# modem2_double.net
KiCad netlist of a schematic drawn in EAGLE
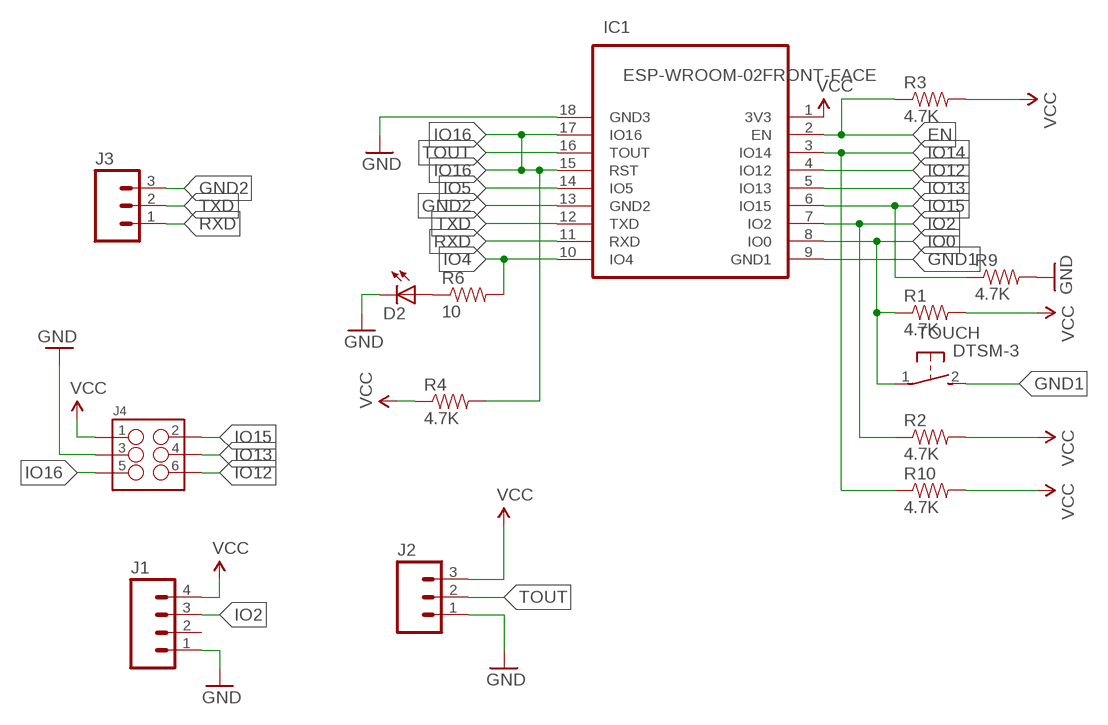
[diagram p0: schematic, sheet 1]

(export (version "E")
  (design (tool "Eeschema 10.0.6"))
  (components
    (comp (ref "D2")
      (value "LEDCHIPLED_0805")
      (footprint "eagle-import:CHIPLED_0805")
      (libsource (lib "eagle-import") (part "LEDCHIPLED_0805"))
    )
    (comp (ref "IC1")
      (value "ESP-WROOM-02FRONT-FACE")
      (footprint "eagle-import:FRONT-FACE")
      (libsource (lib "eagle-import") (part "ESP-WROOM-02FRONT-FACE"))
    )
    (comp (ref "J1")
      (value "M04NO_SILK_ALL_ROUND")
      (footprint "eagle-import:1X04_NO_SILK_ALL_ROUND")
      (libsource (lib "eagle-import") (part "M04NO_SILK_ALL_ROUND"))
    )
    (comp (ref "J2")
      (value "M03PTH")
      (footprint "eagle-import:1X03")
      (libsource (lib "eagle-import") (part "M03PTH"))
    )
    (comp (ref "J3")
      (value "M031X03_NO_SILK")
      (footprint "eagle-import:1X03_NO_SILK")
      (libsource (lib "eagle-import") (part "M031X03_NO_SILK"))
    )
    (comp (ref "J4")
      (value "M03X2SHROUD")
      (footprint "eagle-import:2X3-SHROUDED")
      (libsource (lib "eagle-import") (part "M03X2SHROUD"))
    )
    (comp (ref "R1")
      (value "4.7K")
      (footprint "eagle-import:0805")
      (libsource (lib "eagle-import") (part "RESISTOR0805-RES"))
    )
    (comp (ref "R2")
      (value "4.7K")
      (footprint "eagle-import:0805")
      (libsource (lib "eagle-import") (part "RESISTOR0805-RES"))
    )
    (comp (ref "R3")
      (value "4.7K")
      (footprint "eagle-import:0805")
      (libsource (lib "eagle-import") (part "RESISTOR0805-RES"))
    )
    (comp (ref "R4")
      (value "4.7K")
      (footprint "eagle-import:0805")
      (libsource (lib "eagle-import") (part "RESISTOR0805-RES"))
    )
    (comp (ref "R6")
      (value "10")
      (footprint "eagle-import:0805")
      (libsource (lib "eagle-import") (part "RESISTOR0805-RES"))
    )
    (comp (ref "R9")
      (value "4.7K")
      (footprint "eagle-import:0805")
      (libsource (lib "eagle-import") (part "RESISTOR0805-RES"))
    )
    (comp (ref "R10")
      (value "4.7K")
      (footprint "eagle-import:0805")
      (libsource (lib "eagle-import") (part "RESISTOR0805-RES"))
    )
    (comp (ref "TOUCH")
      (value "DTSM-3")
      (footprint "eagle-import:DTSM-3")
      (libsource (lib "eagle-import") (part "DTSM-3"))
    )
  )
  (nets
    (net (code "1") (name "EN") (class "Default")
      (node (ref "IC1") (pin "2") (pinfunction "EN_2") (pintype "bidirectional"))
      (node (ref "R3") (pin "1") (pinfunction "1_1") (pintype "passive"))
    )
    (net (code "2") (name "GND") (class "Default")
      (node (ref "D2") (pin "C") (pinfunction "C_C") (pintype "passive"))
      (node (ref "IC1") (pin "18") (pinfunction "GND3_18") (pintype "power_in"))
      (node (ref "J1") (pin "1") (pinfunction "1_1") (pintype "passive"))
      (node (ref "J2") (pin "1") (pinfunction "1_1") (pintype "passive"))
      (node (ref "J4") (pin "3") (pinfunction "3_3") (pintype "bidirectional"))
      (node (ref "R9") (pin "2") (pinfunction "2_2") (pintype "passive"))
    )
    (net (code "3") (name "GND1") (class "Default")
      (node (ref "IC1") (pin "9") (pinfunction "GND1_9") (pintype "power_in"))
      (node (ref "TOUCH") (pin "2") (pinfunction "2_2") (pintype "passive"))
    )
    (net (code "4") (name "GND2") (class "Default")
      (node (ref "IC1") (pin "13") (pinfunction "GND2_13") (pintype "power_in"))
      (node (ref "J3") (pin "3") (pinfunction "3_3") (pintype "passive"))
    )
    (net (code "5") (name "IO0") (class "Default")
      (node (ref "IC1") (pin "8") (pinfunction "IO0_8") (pintype "bidirectional"))
      (node (ref "R1") (pin "1") (pinfunction "1_1") (pintype "passive"))
      (node (ref "TOUCH") (pin "1") (pinfunction "1_1") (pintype "passive"))
    )
    (net (code "6") (name "IO2") (class "Default")
      (node (ref "IC1") (pin "7") (pinfunction "IO2_7") (pintype "bidirectional"))
      (node (ref "J1") (pin "3") (pinfunction "3_3") (pintype "passive"))
      (node (ref "R2") (pin "1") (pinfunction "1_1") (pintype "passive"))
    )
    (net (code "7") (name "IO4") (class "Default")
      (node (ref "IC1") (pin "10") (pinfunction "IO4_10") (pintype "bidirectional"))
      (node (ref "R6") (pin "2") (pinfunction "2_2") (pintype "passive"))
    )
    (net (code "8") (name "IO5") (class "Default")
      (node (ref "IC1") (pin "14") (pinfunction "IO5_14") (pintype "open_collector"))
    )
    (net (code "9") (name "IO12") (class "Default")
      (node (ref "IC1") (pin "4") (pinfunction "IO12_4") (pintype "bidirectional"))
      (node (ref "J4") (pin "6") (pinfunction "6_6") (pintype "bidirectional"))
    )
    (net (code "10") (name "IO13") (class "Default")
      (node (ref "IC1") (pin "5") (pinfunction "IO13_5") (pintype "bidirectional"))
      (node (ref "J4") (pin "4") (pinfunction "4_4") (pintype "bidirectional"))
    )
    (net (code "11") (name "IO14") (class "Default")
      (node (ref "IC1") (pin "3") (pinfunction "IO14_3") (pintype "bidirectional"))
      (node (ref "R10") (pin "1") (pinfunction "1_1") (pintype "passive"))
    )
    (net (code "12") (name "IO15") (class "Default")
      (node (ref "IC1") (pin "6") (pinfunction "IO15_6") (pintype "bidirectional"))
      (node (ref "J4") (pin "2") (pinfunction "2_2") (pintype "bidirectional"))
      (node (ref "R9") (pin "1") (pinfunction "1_1") (pintype "passive"))
    )
    (net (code "13") (name "IO16") (class "Default")
      (node (ref "IC1") (pin "15") (pinfunction "RST_15") (pintype "bidirectional"))
      (node (ref "IC1") (pin "17") (pinfunction "IO16_17") (pintype "bidirectional"))
      (node (ref "J4") (pin "5") (pinfunction "5_5") (pintype "bidirectional"))
      (node (ref "R4") (pin "2") (pinfunction "2_2") (pintype "passive"))
    )
    (net (code "14") (name "Net-(D2-PadA)") (class "Default")
      (node (ref "D2") (pin "A") (pinfunction "A_A") (pintype "passive"))
      (node (ref "R6") (pin "1") (pinfunction "1_1") (pintype "passive"))
    )
    (net (code "15") (name "RXD") (class "Default")
      (node (ref "IC1") (pin "11") (pinfunction "RXD_11") (pintype "bidirectional"))
      (node (ref "J3") (pin "1") (pinfunction "1_1") (pintype "passive"))
    )
    (net (code "16") (name "TOUT") (class "Default")
      (node (ref "IC1") (pin "16") (pinfunction "TOUT_16") (pintype "bidirectional"))
      (node (ref "J2") (pin "2") (pinfunction "2_2") (pintype "passive"))
    )
    (net (code "17") (name "TXD") (class "Default")
      (node (ref "IC1") (pin "12") (pinfunction "TXD_12") (pintype "bidirectional"))
      (node (ref "J3") (pin "2") (pinfunction "2_2") (pintype "passive"))
    )
    (net (code "18") (name "VCC") (class "Default")
      (node (ref "IC1") (pin "1") (pinfunction "3V3_1") (pintype "power_in"))
      (node (ref "J1") (pin "4") (pinfunction "4_4") (pintype "passive"))
      (node (ref "J2") (pin "3") (pinfunction "3_3") (pintype "passive"))
      (node (ref "J4") (pin "1") (pinfunction "1_1") (pintype "bidirectional"))
      (node (ref "R1") (pin "2") (pinfunction "2_2") (pintype "passive"))
      (node (ref "R10") (pin "2") (pinfunction "2_2") (pintype "passive"))
      (node (ref "R2") (pin "2") (pinfunction "2_2") (pintype "passive"))
      (node (ref "R3") (pin "2") (pinfunction "2_2") (pintype "passive"))
      (node (ref "R4") (pin "1") (pinfunction "1_1") (pintype "passive"))
    )
    (net (code "19") (name "unconnected-(J1-Pad2)") (class "Default")
      (node (ref "J1") (pin "2") (pinfunction "2_2") (pintype "passive"))
    )
  )
)
